# Main.net
KiCad netlist of a schematic drawn in Altium Designer
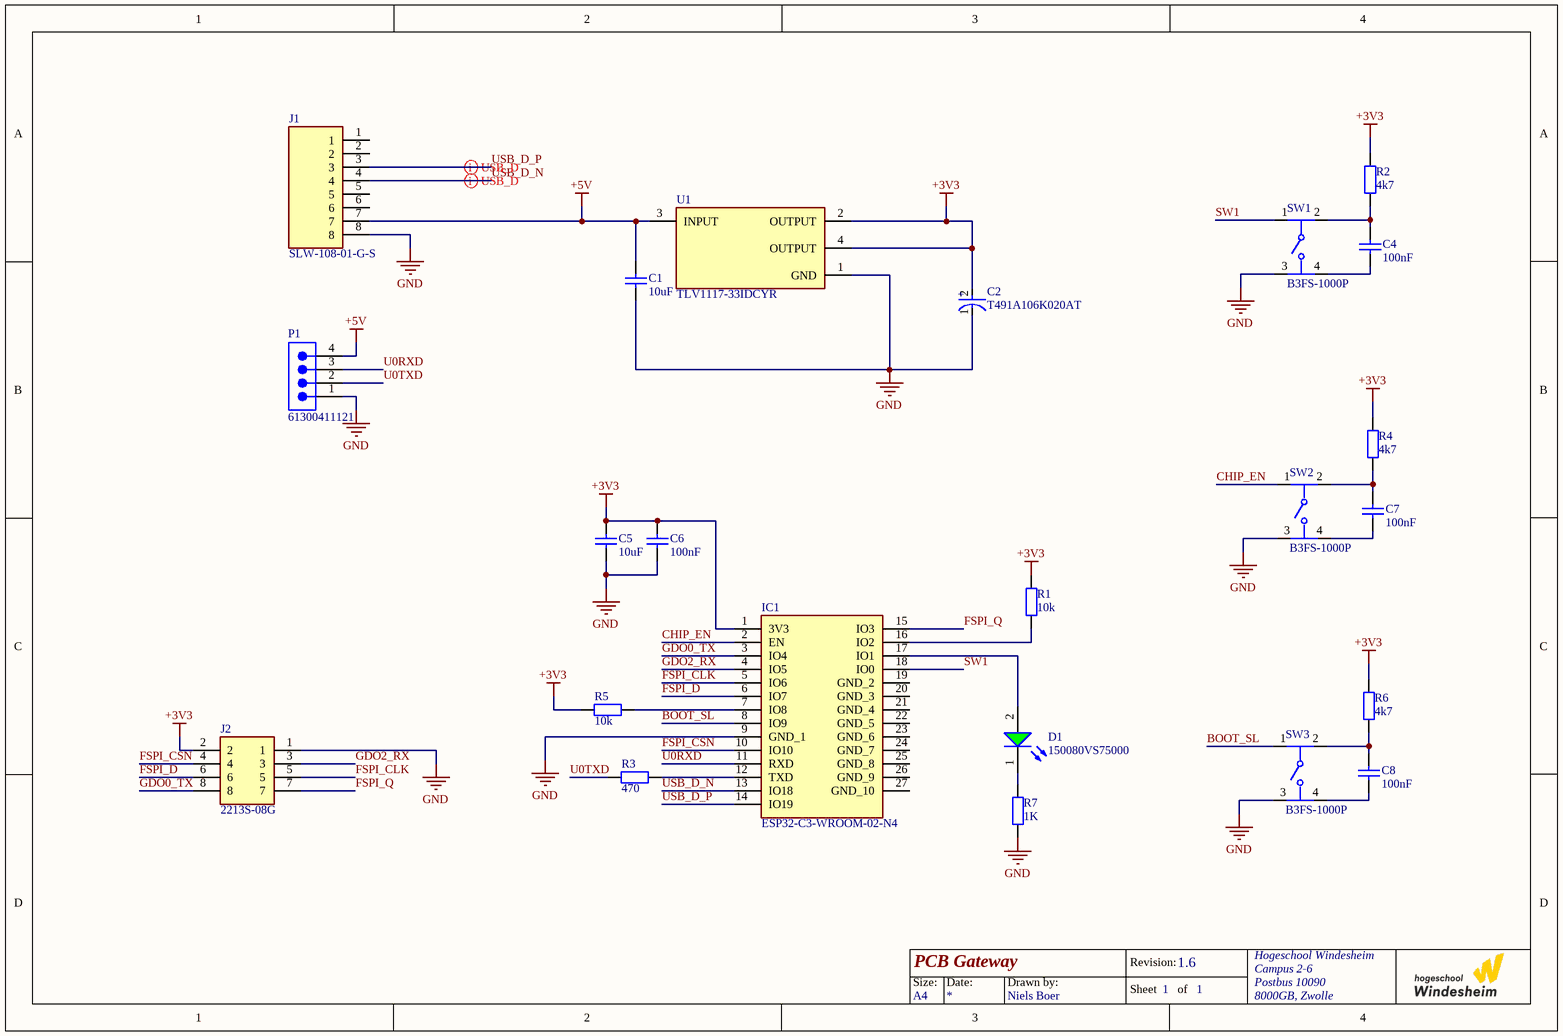
[diagram p0: Main.SchDoc]

(export (version "E")
  (design (tool "Eeschema 10.0.6"))
  (components
    (comp (ref "C1")
      (value "10uF")
      (footprint "C1206")
      (description "SMD Capacitor 1206")
      (fields (field (name "PUBLISHER") "Windesheim"))
      (libsource (lib "KookwekkerLibrary_v5_1") (part "Capacitor_1206"))
    )
    (comp (ref "C2")
      (value "T491A106K020AT")
      (footprint "FP-T491A106K020AT-MFG")
      (description "CAP TANT 10UF 10% 20V 1206")
      (fields (field (name "TOLERANCE") "10%"))
      (libsource (lib "Altium Content Vault") (part "a00bbbee19879c290e62620ae7e47b1"))
    )
    (comp (ref "C4")
      (value "100nF")
      (footprint "C1206")
      (description "SMD Capacitor 1206")
      (fields (field (name "PUBLISHER") "Windesheim"))
      (libsource (lib "KookwekkerLibrary_v5_1") (part "Capacitor_1206"))
    )
    (comp (ref "C5")
      (value "10uF")
      (footprint "C1206")
      (description "SMD Capacitor 1206")
      (fields (field (name "PUBLISHER") "Windesheim"))
      (libsource (lib "KookwekkerLibrary_v5_1") (part "Capacitor_1206"))
    )
    (comp (ref "C6")
      (value "100nF")
      (footprint "C1206")
      (description "SMD Capacitor 1206")
      (fields (field (name "PUBLISHER") "Windesheim"))
      (libsource (lib "KookwekkerLibrary_v5_1") (part "Capacitor_1206"))
    )
    (comp (ref "C7")
      (value "100nF")
      (footprint "C1206")
      (description "SMD Capacitor 1206")
      (fields (field (name "PUBLISHER") "Windesheim"))
      (libsource (lib "KookwekkerLibrary_v5_1") (part "Capacitor_1206"))
    )
    (comp (ref "C8")
      (value "100nF")
      (footprint "C1206")
      (description "SMD Capacitor 1206")
      (fields (field (name "PUBLISHER") "Windesheim"))
      (libsource (lib "KookwekkerLibrary_v5_1") (part "Capacitor_1206"))
    )
    (comp (ref "D1")
      (value "150080VS75000")
      (footprint "WL-SMCW_0805_150080xx75000")
      (libsource (lib "Altium Content Vault") (part "LED_Green_2A-1K"))
    )
    (comp (ref "IC1")
      (value "ESP32-C3-WROOM-02-N4")
      (footprint "SamacSys:ESP32C3WROOM02N4")
      (description "Integrated Circuit")
      (fields (field (name "MOUSER PART NUMBER") "356-ESP32C3WROOM02N4"))
      (libsource (lib "*") (part "ESP32-C3-WROOM-02-N4"))
    )
    (comp (ref "J1")
      (value "SLW-108-01-G-S")
      (footprint "SamacSys:RHDR8W64P0X254_1X8_2032X254X457P")
      (description "Connector")
      (fields (field (name "MOUSER PART NUMBER") "200-SLW10801GS"))
      (libsource (lib "*") (part "SLW-108-01-G-S"))
    )
    (comp (ref "J2")
      (value "2213S-08G")
      (footprint "SamacSys:HDRV8W64P254_2X4_1016X508X874P")
      (description "Connector")
      (libsource (lib "*") (part "2213S-08G"))
    )
    (comp (ref "P1")
      (value "61300411121")
      (footprint "61300411121")
      (libsource (lib "Altium Content Vault") (part "Header_Male_1R_04P"))
    )
    (comp (ref "R1")
      (value "10k")
      (footprint "R1206")
      (description "SMD Resistor 1206")
      (fields (field (name "PUBLISHER") "Windesheim"))
      (libsource (lib "") (part "Resistor_1206_1"))
    )
    (comp (ref "R2")
      (value "4k7")
      (footprint "R1206")
      (description "SMD Resistor 1206")
      (fields (field (name "PUBLISHER") "Windesheim"))
      (libsource (lib "") (part "Resistor_1206_1"))
    )
    (comp (ref "R3")
      (value "470")
      (footprint "R1206")
      (description "SMD Resistor 1206")
      (fields (field (name "PUBLISHER") "Windesheim"))
      (libsource (lib "KookwekkerLibrary_v5_1") (part "Resistor_1206"))
    )
    (comp (ref "R4")
      (value "4k7")
      (footprint "R1206")
      (description "SMD Resistor 1206")
      (fields (field (name "PUBLISHER") "Windesheim"))
      (libsource (lib "") (part "Resistor_1206_1"))
    )
    (comp (ref "R5")
      (value "10k")
      (footprint "R1206")
      (description "SMD Resistor 1206")
      (fields (field (name "PUBLISHER") "Windesheim"))
      (libsource (lib "KookwekkerLibrary_v5_1") (part "Resistor_1206"))
    )
    (comp (ref "R6")
      (value "4k7")
      (footprint "R1206")
      (description "SMD Resistor 1206")
      (fields (field (name "PUBLISHER") "Windesheim"))
      (libsource (lib "") (part "Resistor_1206_1"))
    )
    (comp (ref "R7")
      (value "1K")
      (footprint "R1206")
      (description "SMD Resistor 1206")
      (fields (field (name "PUBLISHER") "Windesheim"))
      (libsource (lib "") (part "Resistor_1206_1"))
    )
    (comp (ref "SW1")
      (value "B3FS-1000P")
      (footprint "FP-B3FS-1000P-MFG")
      (description "SWITCH TACTILE SPST-NO 0.05A 24V")
      (libsource (lib "Altium Content Vault") (part "b8895f3f4cefb76e1819d2863dba89b"))
    )
    (comp (ref "SW2")
      (value "B3FS-1000P")
      (footprint "FP-B3FS-1000P-MFG")
      (description "SWITCH TACTILE SPST-NO 0.05A 24V")
      (libsource (lib "Altium Content Vault") (part "b8895f3f4cefb76e1819d2863dba89b"))
    )
    (comp (ref "SW3")
      (value "B3FS-1000P")
      (footprint "FP-B3FS-1000P-MFG")
      (description "SWITCH TACTILE SPST-NO 0.05A 24V")
      (libsource (lib "Altium Content Vault") (part "b8895f3f4cefb76e1819d2863dba89b"))
    )
    (comp (ref "U1")
      (value "TLV1117-33IDCYR")
      (footprint "FP-DCY0004A-MFG")
      (description "IC REG LIN 3.3V 800MA SOT223-4")
      (fields
        (field (name "MANUFACTURER") "Texas Instruments")
        (field (name "OCTOPART") "https://octopart.com/tlv1117-33idcyr-texas+instruments-669250")
      )
      (libsource (lib "Altium Content Vault") (part "d420fb9686013fb832e66295cdf4acf"))
    )
  )
  (nets
    (net (code "1") (name "+3V3") (class "Default")
      (node (ref "C2") (pin "2") (pinfunction "A_2") (pintype "passive"))
      (node (ref "C5") (pin "2") (pinfunction "2_2") (pintype "passive"))
      (node (ref "C6") (pin "2") (pinfunction "2_2") (pintype "passive"))
      (node (ref "IC1") (pin "1") (pinfunction "3V3_1") (pintype "passive"))
      (node (ref "J2") (pin "2") (pinfunction "2_2") (pintype "passive"))
      (node (ref "R1") (pin "2") (pinfunction "2_2") (pintype "passive"))
      (node (ref "R2") (pin "2") (pinfunction "2_2") (pintype "passive"))
      (node (ref "R4") (pin "2") (pinfunction "2_2") (pintype "passive"))
      (node (ref "R5") (pin "1") (pinfunction "1_1") (pintype "passive"))
      (node (ref "R6") (pin "2") (pinfunction "2_2") (pintype "passive"))
      (node (ref "U1") (pin "2") (pinfunction "OUTPUT_2") (pintype "power_in"))
      (node (ref "U1") (pin "4") (pinfunction "OUTPUT_4") (pintype "power_in"))
    )
    (net (code "2") (name "+5V") (class "Default")
      (node (ref "C1") (pin "2") (pinfunction "2_2") (pintype "passive"))
      (node (ref "J1") (pin "7") (pinfunction "7_7") (pintype "passive"))
      (node (ref "P1") (pin "4") (pinfunction "4_4") (pintype "passive"))
      (node (ref "U1") (pin "3") (pinfunction "INPUT_3") (pintype "power_in"))
    )
    (net (code "4") (name "/BOOT_SL") (class "Default")
      (node (ref "IC1") (pin "8") (pinfunction "IO9_8") (pintype "passive"))
      (node (ref "SW3") (pin "1") (pinfunction "1_1") (pintype "passive"))
    )
    (net (code "5") (name "/CHIP_EN") (class "Default")
      (node (ref "IC1") (pin "2") (pinfunction "EN_2") (pintype "passive"))
      (node (ref "SW2") (pin "1") (pinfunction "1_1") (pintype "passive"))
    )
    (net (code "6") (name "/FSPI_CLK") (class "Default")
      (node (ref "IC1") (pin "5") (pinfunction "IO6_5") (pintype "passive"))
      (node (ref "J2") (pin "5") (pinfunction "5_5") (pintype "passive"))
    )
    (net (code "7") (name "/FSPI_CSN") (class "Default")
      (node (ref "IC1") (pin "10") (pinfunction "IO10_10") (pintype "passive"))
      (node (ref "J2") (pin "4") (pinfunction "4_4") (pintype "passive"))
    )
    (net (code "8") (name "/FSPI_D") (class "Default")
      (node (ref "IC1") (pin "6") (pinfunction "IO7_6") (pintype "passive"))
      (node (ref "J2") (pin "6") (pinfunction "6_6") (pintype "passive"))
    )
    (net (code "9") (name "/FSPI_Q") (class "Default")
      (node (ref "IC1") (pin "15") (pinfunction "IO3_15") (pintype "passive"))
      (node (ref "J2") (pin "7") (pinfunction "7_7") (pintype "passive"))
    )
    (net (code "10") (name "/GDO0_TX") (class "Default")
      (node (ref "IC1") (pin "3") (pinfunction "IO4_3") (pintype "passive"))
      (node (ref "J2") (pin "8") (pinfunction "8_8") (pintype "passive"))
    )
    (net (code "11") (name "/GDO2_RX") (class "Default")
      (node (ref "IC1") (pin "4") (pinfunction "IO5_4") (pintype "passive"))
      (node (ref "J2") (pin "3") (pinfunction "3_3") (pintype "passive"))
    )
    (net (code "12") (name "/SW1") (class "Default")
      (node (ref "IC1") (pin "18") (pinfunction "IO0_18") (pintype "passive"))
      (node (ref "SW1") (pin "1") (pinfunction "1_1") (pintype "passive"))
    )
    (net (code "13") (name "/U0RXD") (class "Default")
      (node (ref "IC1") (pin "11") (pinfunction "RXD_11") (pintype "passive"))
      (node (ref "P1") (pin "3") (pinfunction "3_3") (pintype "passive"))
    )
    (net (code "14") (name "/U0TXD") (class "Default")
      (node (ref "P1") (pin "2") (pinfunction "2_2") (pintype "passive"))
      (node (ref "R3") (pin "1") (pinfunction "1_1") (pintype "passive"))
    )
    (net (code "15") (name "/USB_D_N") (class "Default")
      (node (ref "IC1") (pin "13") (pinfunction "IO18_13") (pintype "passive"))
      (node (ref "J1") (pin "4") (pinfunction "4_4") (pintype "passive"))
    )
    (net (code "16") (name "/USB_D_P") (class "Default")
      (node (ref "IC1") (pin "14") (pinfunction "IO19_14") (pintype "passive"))
      (node (ref "J1") (pin "3") (pinfunction "3_3") (pintype "passive"))
    )
    (net (code "17") (name "GND") (class "Default")
      (node (ref "C1") (pin "1") (pinfunction "1_1") (pintype "passive"))
      (node (ref "C2") (pin "1") (pinfunction "C_1") (pintype "passive"))
      (node (ref "C5") (pin "1") (pinfunction "1_1") (pintype "passive"))
      (node (ref "C6") (pin "1") (pinfunction "1_1") (pintype "passive"))
      (node (ref "IC1") (pin "9") (pinfunction "GND_1_9") (pintype "passive"))
      (node (ref "J1") (pin "8") (pinfunction "8_8") (pintype "passive"))
      (node (ref "J2") (pin "1") (pinfunction "1_1") (pintype "passive"))
      (node (ref "P1") (pin "1") (pinfunction "1_1") (pintype "passive"))
      (node (ref "R7") (pin "1") (pinfunction "1_1") (pintype "passive"))
      (node (ref "SW1") (pin "3") (pinfunction "3_3") (pintype "passive"))
      (node (ref "SW2") (pin "3") (pinfunction "3_3") (pintype "passive"))
      (node (ref "SW3") (pin "3") (pinfunction "3_3") (pintype "passive"))
      (node (ref "U1") (pin "1") (pinfunction "GND_1") (pintype "power_in"))
    )
    (net (code "18") (name "Net-(C4-Pad1)") (class "Default")
      (node (ref "C4") (pin "1") (pinfunction "1_1") (pintype "passive"))
      (node (ref "SW1") (pin "4") (pinfunction "4_4") (pintype "passive"))
    )
    (net (code "19") (name "Net-(C4-Pad2)") (class "Default")
      (node (ref "C4") (pin "2") (pinfunction "2_2") (pintype "passive"))
      (node (ref "R2") (pin "1") (pinfunction "1_1") (pintype "passive"))
      (node (ref "SW1") (pin "2") (pinfunction "2_2") (pintype "passive"))
    )
    (net (code "20") (name "Net-(C7-Pad1)") (class "Default")
      (node (ref "C7") (pin "1") (pinfunction "1_1") (pintype "passive"))
      (node (ref "SW2") (pin "4") (pinfunction "4_4") (pintype "passive"))
    )
    (net (code "21") (name "Net-(C7-Pad2)") (class "Default")
      (node (ref "C7") (pin "2") (pinfunction "2_2") (pintype "passive"))
      (node (ref "R4") (pin "1") (pinfunction "1_1") (pintype "passive"))
      (node (ref "SW2") (pin "2") (pinfunction "2_2") (pintype "passive"))
    )
    (net (code "22") (name "Net-(C8-Pad1)") (class "Default")
      (node (ref "C8") (pin "1") (pinfunction "1_1") (pintype "passive"))
      (node (ref "SW3") (pin "4") (pinfunction "4_4") (pintype "passive"))
    )
    (net (code "23") (name "Net-(C8-Pad2)") (class "Default")
      (node (ref "C8") (pin "2") (pinfunction "2_2") (pintype "passive"))
      (node (ref "R6") (pin "1") (pinfunction "1_1") (pintype "passive"))
      (node (ref "SW3") (pin "2") (pinfunction "2_2") (pintype "passive"))
    )
    (net (code "24") (name "Net-(D1-A)") (class "Default")
      (node (ref "D1") (pin "2") (pinfunction "A_2") (pintype "passive"))
      (node (ref "IC1") (pin "17") (pinfunction "IO1_17") (pintype "passive"))
    )
    (net (code "25") (name "Net-(D1-K)") (class "Default")
      (node (ref "D1") (pin "1") (pinfunction "K_1") (pintype "passive"))
      (node (ref "R7") (pin "2") (pinfunction "2_2") (pintype "passive"))
    )
    (net (code "26") (name "Net-(IC1-IO2)") (class "Default")
      (node (ref "IC1") (pin "16") (pinfunction "IO2_16") (pintype "passive"))
      (node (ref "R1") (pin "1") (pinfunction "1_1") (pintype "passive"))
    )
    (net (code "27") (name "Net-(IC1-IO8)") (class "Default")
      (node (ref "IC1") (pin "7") (pinfunction "IO8_7") (pintype "passive"))
      (node (ref "R5") (pin "2") (pinfunction "2_2") (pintype "passive"))
    )
    (net (code "28") (name "Net-(IC1-TXD)") (class "Default")
      (node (ref "IC1") (pin "12") (pinfunction "TXD_12") (pintype "passive"))
      (node (ref "R3") (pin "2") (pinfunction "2_2") (pintype "passive"))
    )
    (net (code "29") (name "unconnected-(IC1-GND_2-Pad19)") (class "Default")
      (node (ref "IC1") (pin "19") (pinfunction "GND_2_19") (pintype "passive"))
    )
    (net (code "30") (name "unconnected-(IC1-GND_3-Pad20)") (class "Default")
      (node (ref "IC1") (pin "20") (pinfunction "GND_3_20") (pintype "passive"))
    )
    (net (code "31") (name "unconnected-(IC1-GND_4-Pad21)") (class "Default")
      (node (ref "IC1") (pin "21") (pinfunction "GND_4_21") (pintype "passive"))
    )
    (net (code "32") (name "unconnected-(IC1-GND_5-Pad22)") (class "Default")
      (node (ref "IC1") (pin "22") (pinfunction "GND_5_22") (pintype "passive"))
    )
    (net (code "33") (name "unconnected-(IC1-GND_6-Pad23)") (class "Default")
      (node (ref "IC1") (pin "23") (pinfunction "GND_6_23") (pintype "passive"))
    )
    (net (code "34") (name "unconnected-(IC1-GND_7-Pad24)") (class "Default")
      (node (ref "IC1") (pin "24") (pinfunction "GND_7_24") (pintype "passive"))
    )
    (net (code "35") (name "unconnected-(IC1-GND_8-Pad25)") (class "Default")
      (node (ref "IC1") (pin "25") (pinfunction "GND_8_25") (pintype "passive"))
    )
    (net (code "36") (name "unconnected-(IC1-GND_9-Pad26)") (class "Default")
      (node (ref "IC1") (pin "26") (pinfunction "GND_9_26") (pintype "passive"))
    )
    (net (code "37") (name "unconnected-(IC1-GND_10-Pad27)") (class "Default")
      (node (ref "IC1") (pin "27") (pinfunction "GND_10_27") (pintype "passive"))
    )
    (net (code "38") (name "unconnected-(J1-Pad1)") (class "Default")
      (node (ref "J1") (pin "1") (pinfunction "1_1") (pintype "passive"))
    )
    (net (code "39") (name "unconnected-(J1-Pad2)") (class "Default")
      (node (ref "J1") (pin "2") (pinfunction "2_2") (pintype "passive"))
    )
    (net (code "40") (name "unconnected-(J1-Pad5)") (class "Default")
      (node (ref "J1") (pin "5") (pinfunction "5_5") (pintype "passive"))
    )
    (net (code "41") (name "unconnected-(J1-Pad6)") (class "Default")
      (node (ref "J1") (pin "6") (pinfunction "6_6") (pintype "passive"))
    )
  )
)
